# TC364_MainBoard_Power_V1_2.net
KiCad netlist of a schematic drawn in Altium Designer
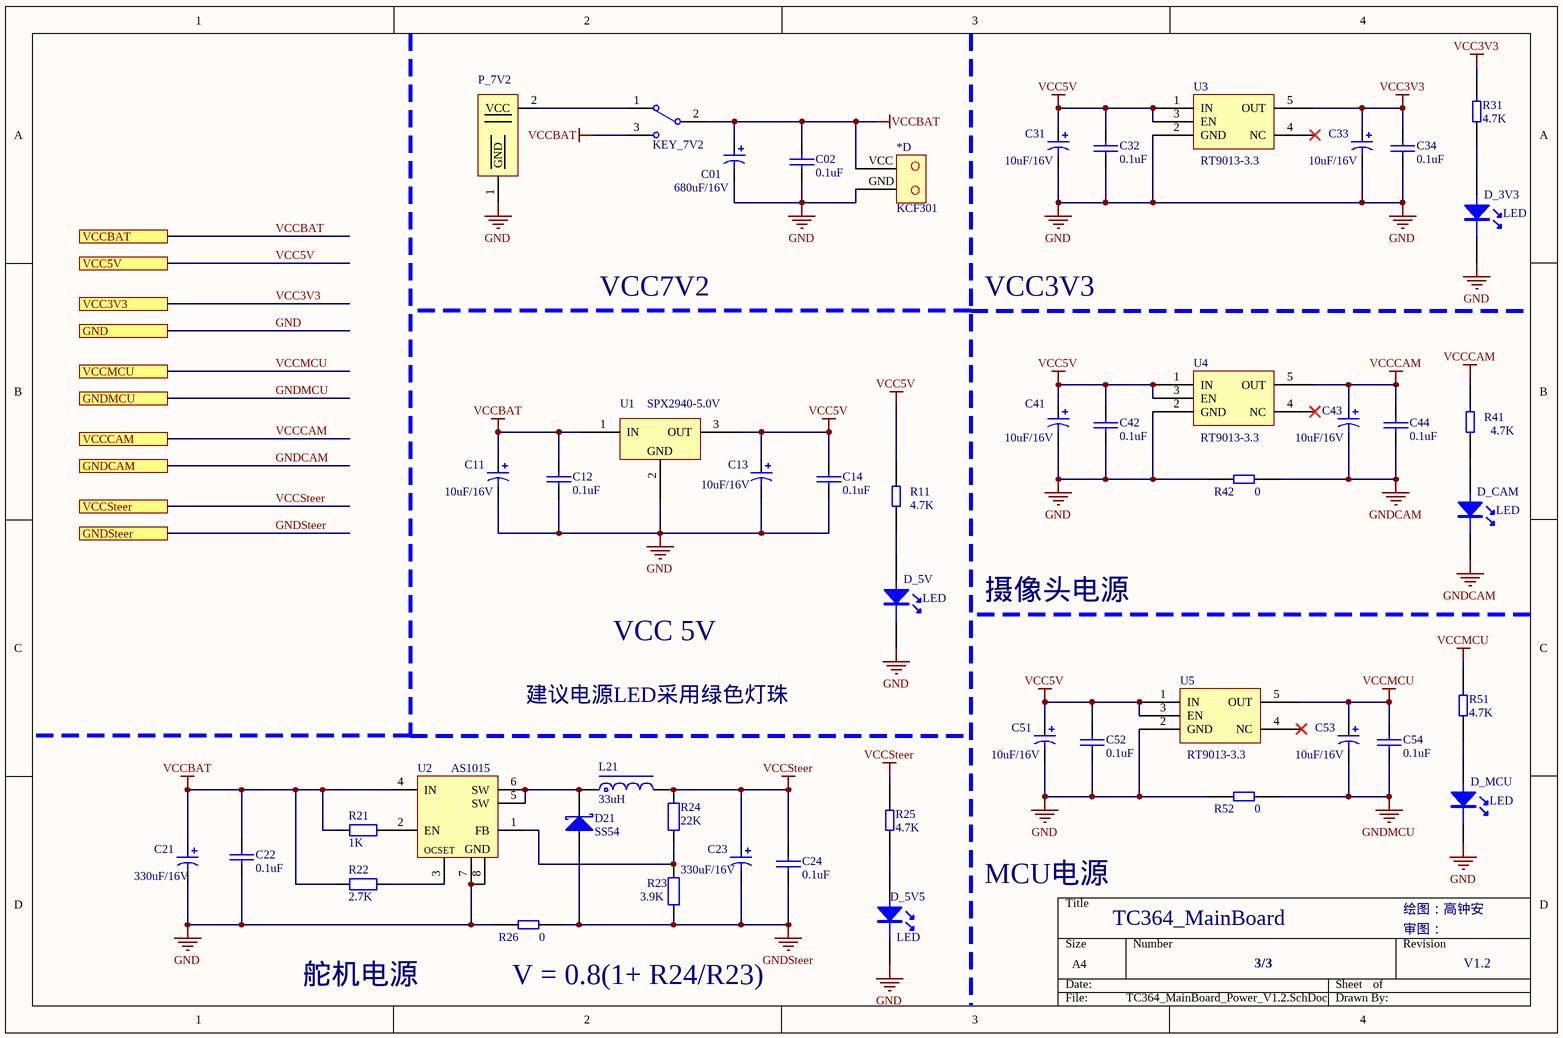
[diagram p0: TC364_MainBoard_Power_V1.2.SchDoc]

(export (version "E")
  (design (tool "Eeschema 10.0.6"))
  (components
    (comp (ref "*") (value "KCF301") (footprint "KF301-2P") (libsource (lib "BaseLib_SCH") (part "KCF301")))
    (comp (ref "C01")
      (value "680uF/16V")
      (footprint "CAP 3.5*8*11.5 - GD")
      (description "Polarized Capacitor (Radial)")
      (fields (field (name "PUBLISHER") "Altium Limited"))
      (libsource (lib "Miscellaneous Devices") (part "Cap Pol1"))
    )
    (comp (ref "C02")
      (value "0.1uF")
      (footprint "0805C")
      (description "Capacitor")
      (libsource (lib "Protel99Lib_SCH") (part "CAP"))
    )
    (comp (ref "C11")
      (value "10uF/16V")
      (footprint "CASE-A_3216")
      (description "Polarized Capacitor (Radial)")
      (fields (field (name "PUBLISHER") "Altium Limited"))
      (libsource (lib "Miscellaneous Devices") (part "Cap Pol1"))
    )
    (comp (ref "C12")
      (value "0.1uF")
      (footprint "0805C")
      (description "Capacitor")
      (libsource (lib "Protel99Lib_SCH") (part "CAP"))
    )
    (comp (ref "C13")
      (value "10uF/16V")
      (footprint "CASE-A_3216")
      (description "Polarized Capacitor (Radial)")
      (fields (field (name "PUBLISHER") "Altium Limited"))
      (libsource (lib "Miscellaneous Devices") (part "Cap Pol1"))
    )
    (comp (ref "C14")
      (value "0.1uF")
      (footprint "0805C")
      (description "Capacitor")
      (libsource (lib "Protel99Lib_SCH") (part "CAP"))
    )
    (comp (ref "C21")
      (value "330uF/16V")
      (footprint "CAP 2.5*6.3*11.2 - BK")
      (description "Polarized Capacitor (Radial)")
      (fields (field (name "PUBLISHER") "Altium Limited"))
      (libsource (lib "Miscellaneous Devices") (part "Cap Pol1"))
    )
    (comp (ref "C22")
      (value "0.1uF")
      (footprint "0805C")
      (description "Capacitor")
      (libsource (lib "Protel99Lib_SCH") (part "CAP"))
    )
    (comp (ref "C23")
      (value "330uF/16V")
      (footprint "CAP 2.5*6.3*11.2 - BK")
      (description "Polarized Capacitor (Radial)")
      (fields (field (name "PUBLISHER") "Altium Limited"))
      (libsource (lib "Miscellaneous Devices") (part "Cap Pol1"))
    )
    (comp (ref "C24")
      (value "0.1uF")
      (footprint "0805C")
      (description "Capacitor")
      (libsource (lib "Protel99Lib_SCH") (part "CAP"))
    )
    (comp (ref "C31")
      (value "10uF/16V")
      (footprint "CASE-A_3216")
      (description "Polarized Capacitor (Radial)")
      (fields (field (name "PUBLISHER") "Altium Limited"))
      (libsource (lib "Miscellaneous Devices") (part "Cap Pol1"))
    )
    (comp (ref "C32")
      (value "0.1uF")
      (footprint "0805C")
      (description "Capacitor")
      (libsource (lib "Protel99Lib_SCH") (part "CAP"))
    )
    (comp (ref "C33")
      (value "10uF/16V")
      (footprint "CASE-A_3216")
      (description "Polarized Capacitor (Radial)")
      (fields (field (name "PUBLISHER") "Altium Limited"))
      (libsource (lib "Miscellaneous Devices") (part "Cap Pol1"))
    )
    (comp (ref "C34")
      (value "0.1uF")
      (footprint "0805C")
      (description "Capacitor")
      (libsource (lib "Protel99Lib_SCH") (part "CAP"))
    )
    (comp (ref "C41")
      (value "10uF/16V")
      (footprint "CASE-A_3216")
      (description "Polarized Capacitor (Radial)")
      (fields (field (name "PUBLISHER") "Altium Limited"))
      (libsource (lib "Miscellaneous Devices") (part "Cap Pol1"))
    )
    (comp (ref "C42")
      (value "0.1uF")
      (footprint "0805C")
      (description "Capacitor")
      (libsource (lib "Protel99Lib_SCH") (part "CAP"))
    )
    (comp (ref "C43")
      (value "10uF/16V")
      (footprint "CASE-A_3216")
      (description "Polarized Capacitor (Radial)")
      (fields (field (name "PUBLISHER") "Altium Limited"))
      (libsource (lib "Miscellaneous Devices") (part "Cap Pol1"))
    )
    (comp (ref "C44")
      (value "0.1uF")
      (footprint "0805C")
      (description "Capacitor")
      (libsource (lib "Protel99Lib_SCH") (part "CAP"))
    )
    (comp (ref "C51")
      (value "10uF/16V")
      (footprint "CASE-A_3216")
      (description "Polarized Capacitor (Radial)")
      (fields (field (name "PUBLISHER") "Altium Limited"))
      (libsource (lib "Miscellaneous Devices") (part "Cap Pol1"))
    )
    (comp (ref "C52")
      (value "0.1uF")
      (footprint "0805C")
      (description "Capacitor")
      (libsource (lib "Protel99Lib_SCH") (part "CAP"))
    )
    (comp (ref "C53")
      (value "10uF/16V")
      (footprint "CASE-A_3216")
      (description "Polarized Capacitor (Radial)")
      (fields (field (name "PUBLISHER") "Altium Limited"))
      (libsource (lib "Miscellaneous Devices") (part "Cap Pol1"))
    )
    (comp (ref "C54")
      (value "0.1uF")
      (footprint "0805C")
      (description "Capacitor")
      (libsource (lib "Protel99Lib_SCH") (part "CAP"))
    )
    (comp (ref "D21")
      (value "SS54")
      (footprint "SMA")
      (description "肖特基二极管")
      (libsource (lib "0.2 -  二极管-整流桥") (part "SS34"))
    )
    (comp (ref "D_3V3")
      (value "LED")
      (footprint "0805_LED_S1")
      (description "发光二极管")
      (libsource (lib "jianing") (part "LED"))
    )
    (comp (ref "D_5V")
      (value "LED")
      (footprint "0805_LED_S1")
      (description "发光二极管")
      (libsource (lib "jianing") (part "LED"))
    )
    (comp (ref "D_5V5")
      (value "LED")
      (footprint "0805_LED_S1")
      (description "发光二极管")
      (libsource (lib "jianing") (part "LED"))
    )
    (comp (ref "D_CAM")
      (value "LED")
      (footprint "0805_LED_S1")
      (description "发光二极管")
      (libsource (lib "jianing") (part "LED"))
    )
    (comp (ref "D_MCU")
      (value "LED")
      (footprint "0805_LED_S1")
      (description "发光二极管")
      (libsource (lib "jianing") (part "LED"))
    )
    (comp (ref "KEY_7V2")
      (value "SS-12F23")
      (footprint "KEY_7V2")
      (description "1路波动开关")
      (fields (field (name "版权归属") "封装库来自淘宝 ID：黄晶宝石"))
      (libsource (lib "0.7 - 常用按键-开关") (part "SSW-1P"))
    )
    (comp (ref "L21")
      (value "33uH")
      (footprint "7*7 L")
      (description "功率屏蔽电感")
      (fields (field (name "版权归属") "封装库来自淘宝 ID：黄晶宝石"))
      (libsource (lib "0.1 - 电阻-电容-电感") (part "L-CDRH"))
    )
    (comp (ref "P_7V2")
      (value "T_Type_Adapter")
      (footprint "T_Type_Adapter")
      (libsource (lib "Schlib1") (part "T_Type_Adapter"))
    )
    (comp (ref "R11") (value "4.7K") (footprint "0805R") (libsource (lib "BaseLib_SCH") (part "RES")))
    (comp (ref "R21")
      (value "1K")
      (footprint "0805R")
      (description "贴片电阻")
      (fields (field (name "版权归属") "源创客"))
      (libsource (lib "jianing") (part "RES"))
    )
    (comp (ref "R22")
      (value "2.7K")
      (footprint "0805R")
      (description "贴片电阻")
      (fields (field (name "版权归属") "源创客"))
      (libsource (lib "jianing") (part "RES"))
    )
    (comp (ref "R23")
      (value "3.9K")
      (footprint "0805R")
      (description "贴片电阻")
      (fields (field (name "版权归属") "源创客"))
      (libsource (lib "jianing") (part "RES"))
    )
    (comp (ref "R24")
      (value "22K")
      (footprint "0805R")
      (description "贴片电阻")
      (fields (field (name "版权归属") "源创客"))
      (libsource (lib "jianing") (part "RES"))
    )
    (comp (ref "R25") (value "4.7K") (footprint "0805R") (libsource (lib "BaseLib_SCH") (part "RES")))
    (comp (ref "R26") (value "0") (footprint "0805R") (libsource (lib "BaseLib_SCH") (part "RES")))
    (comp (ref "R31") (value "4.7K") (footprint "0805R") (libsource (lib "BaseLib_SCH") (part "RES")))
    (comp (ref "R41") (value "4.7K") (footprint "0805R") (libsource (lib "BaseLib_SCH") (part "RES")))
    (comp (ref "R42") (value "0") (footprint "0805R") (libsource (lib "BaseLib_SCH") (part "RES")))
    (comp (ref "R51") (value "4.7K") (footprint "0805R") (libsource (lib "BaseLib_SCH") (part "RES")))
    (comp (ref "R52") (value "0") (footprint "0805R") (libsource (lib "BaseLib_SCH") (part "RES")))
    (comp (ref "U1")
      (value "SPX2940-5.0V")
      (footprint "TO-220(TO-220-3)")
      (description "5V稳压芯片")
      (fields (field (name "版权归属") "封装库来自淘宝 ID：黄晶宝石"))
      (libsource (lib "1.1 - 电源类芯片") (part "LM2940"))
    )
    (comp (ref "U2")
      (value "AS1015")
      (footprint "SOP-8_150mil")
      (description "可调升压芯片")
      (libsource (lib "1.0 - 常见芯片") (part "AS1015"))
    )
    (comp (ref "U3")
      (value "RT9013-3.3")
      (footprint "SOT-23-5")
      (libsource (lib "jianing") (part "RT9013-3.3"))
    )
    (comp (ref "U4")
      (value "RT9013-3.3")
      (footprint "SOT-23-5")
      (libsource (lib "jianing") (part "RT9013-3.3"))
    )
    (comp (ref "U5")
      (value "RT9013-3.3")
      (footprint "SOT-23-5")
      (libsource (lib "jianing") (part "RT9013-3.3"))
    )
  )
  (nets
    (net (code "1") (name "GND") (class "Default")
      (node (ref "C01") (pin "2") (pinfunction "2_2") (pintype "passive"))
      (node (ref "C02") (pin "2") (pinfunction "2_2") (pintype "passive"))
      (node (ref "C11") (pin "2") (pinfunction "2_2") (pintype "passive"))
      (node (ref "C12") (pin "2") (pinfunction "2_2") (pintype "passive"))
      (node (ref "C13") (pin "2") (pinfunction "2_2") (pintype "passive"))
      (node (ref "C14") (pin "2") (pinfunction "2_2") (pintype "passive"))
      (node (ref "C21") (pin "2") (pinfunction "2_2") (pintype "passive"))
      (node (ref "C22") (pin "2") (pinfunction "2_2") (pintype "passive"))
      (node (ref "C31") (pin "2") (pinfunction "2_2") (pintype "passive"))
      (node (ref "C32") (pin "2") (pinfunction "2_2") (pintype "passive"))
      (node (ref "C33") (pin "2") (pinfunction "2_2") (pintype "passive"))
      (node (ref "C34") (pin "2") (pinfunction "2_2") (pintype "passive"))
      (node (ref "C41") (pin "2") (pinfunction "2_2") (pintype "passive"))
      (node (ref "C42") (pin "2") (pinfunction "2_2") (pintype "passive"))
      (node (ref "C51") (pin "2") (pinfunction "2_2") (pintype "passive"))
      (node (ref "C52") (pin "2") (pinfunction "2_2") (pintype "passive"))
      (node (ref "D_3V3") (pin "K") (pinfunction "2_K") (pintype "passive"))
      (node (ref "D_5V") (pin "K") (pinfunction "2_K") (pintype "passive"))
      (node (ref "D_5V5") (pin "K") (pinfunction "2_K") (pintype "passive"))
      (node (ref "P_7V2") (pin "1") (pinfunction "GND_1") (pintype "passive"))
      (node (ref "R26") (pin "2") (pinfunction "2_2") (pintype "passive"))
      (node (ref "R42") (pin "2") (pinfunction "2_2") (pintype "passive"))
      (node (ref "R52") (pin "2") (pinfunction "2_2") (pintype "passive"))
      (node (ref "U1") (pin "2") (pinfunction "GND_2") (pintype "power_in"))
      (node (ref "U2") (pin "7") (pinfunction "GND_7") (pintype "power_in"))
      (node (ref "U2") (pin "8") (pinfunction "GND_8") (pintype "power_in"))
      (node (ref "U3") (pin "2") (pinfunction "GND_2") (pintype "passive"))
      (node (ref "U4") (pin "2") (pinfunction "GND_2") (pintype "passive"))
      (node (ref "U5") (pin "2") (pinfunction "GND_2") (pintype "passive"))
    )
    (net (code "2") (name "GNDCAM") (class "Default")
      (node (ref "C43") (pin "2") (pinfunction "2_2") (pintype "passive"))
      (node (ref "C44") (pin "2") (pinfunction "2_2") (pintype "passive"))
      (node (ref "D_CAM") (pin "K") (pinfunction "2_K") (pintype "passive"))
      (node (ref "R42") (pin "1") (pinfunction "1_1") (pintype "passive"))
    )
    (net (code "3") (name "GNDMCU") (class "Default")
      (node (ref "C53") (pin "2") (pinfunction "2_2") (pintype "passive"))
      (node (ref "C54") (pin "2") (pinfunction "2_2") (pintype "passive"))
      (node (ref "R52") (pin "1") (pinfunction "1_1") (pintype "passive"))
    )
    (net (code "4") (name "GNDSteer") (class "Default")
      (node (ref "C23") (pin "2") (pinfunction "2_2") (pintype "passive"))
      (node (ref "C24") (pin "2") (pinfunction "2_2") (pintype "passive"))
      (node (ref "D21") (pin "1") (pinfunction "A_1") (pintype "passive"))
      (node (ref "R23") (pin "2") (pinfunction "2_2") (pintype "passive"))
      (node (ref "R26") (pin "1") (pinfunction "1_1") (pintype "passive"))
    )
    (net (code "5") (name "Net-(D21-K)") (class "Default")
      (node (ref "D21") (pin "2") (pinfunction "K_2") (pintype "passive"))
      (node (ref "L21") (pin "1") (pinfunction "1_1") (pintype "passive"))
      (node (ref "U2") (pin "5") (pinfunction "SW_5") (pintype "power_in"))
      (node (ref "U2") (pin "6") (pinfunction "SW_6") (pintype "power_in"))
    )
    (net (code "6") (name "Net-(D_3V3-1)") (class "Default")
      (node (ref "D_3V3") (pin "A") (pinfunction "1_A") (pintype "passive"))
      (node (ref "R31") (pin "2") (pinfunction "2_2") (pintype "passive"))
    )
    (net (code "7") (name "Net-(D_5V-1)") (class "Default")
      (node (ref "D_5V") (pin "A") (pinfunction "1_A") (pintype "passive"))
      (node (ref "R11") (pin "2") (pinfunction "2_2") (pintype "passive"))
    )
    (net (code "8") (name "Net-(D_5V5-1)") (class "Default")
      (node (ref "D_5V5") (pin "A") (pinfunction "1_A") (pintype "passive"))
      (node (ref "R25") (pin "2") (pinfunction "2_2") (pintype "passive"))
    )
    (net (code "9") (name "Net-(D_CAM-1)") (class "Default")
      (node (ref "D_CAM") (pin "A") (pinfunction "1_A") (pintype "passive"))
      (node (ref "R41") (pin "2") (pinfunction "2_2") (pintype "passive"))
    )
    (net (code "10") (name "Net-(D_MCU-1)") (class "Default")
      (node (ref "D_MCU") (pin "A") (pinfunction "1_A") (pintype "passive"))
      (node (ref "R51") (pin "2") (pinfunction "2_2") (pintype "passive"))
    )
    (net (code "11") (name "Net-(P_7V2-VCC)") (class "Default")
      (node (ref "KEY_7V2") (pin "1") (pinfunction "1_1") (pintype "passive"))
      (node (ref "P_7V2") (pin "2") (pinfunction "VCC_2") (pintype "passive"))
    )
    (net (code "12") (name "Net-(U2-EN)") (class "Default")
      (node (ref "R21") (pin "1") (pinfunction "1_1") (pintype "passive"))
      (node (ref "U2") (pin "2") (pinfunction "EN_2") (pintype "power_in"))
    )
    (net (code "13") (name "Net-(U2-FB)") (class "Default")
      (node (ref "R23") (pin "1") (pinfunction "1_1") (pintype "passive"))
      (node (ref "R24") (pin "2") (pinfunction "2_2") (pintype "passive"))
      (node (ref "U2") (pin "1") (pinfunction "FB_1") (pintype "power_in"))
    )
    (net (code "14") (name "Net-(U2-OCSET)") (class "Default")
      (node (ref "R22") (pin "1") (pinfunction "1_1") (pintype "passive"))
      (node (ref "U2") (pin "3") (pinfunction "OCSET_3") (pintype "power_in"))
    )
    (net (code "15") (name "VCC3V3") (class "Default")
      (node (ref "C33") (pin "1") (pinfunction "1_1") (pintype "passive"))
      (node (ref "C34") (pin "1") (pinfunction "1_1") (pintype "passive"))
      (node (ref "R31") (pin "1") (pinfunction "1_1") (pintype "passive"))
      (node (ref "U3") (pin "5") (pinfunction "OUT_5") (pintype "passive"))
    )
    (net (code "16") (name "VCC5V") (class "Default")
      (node (ref "C13") (pin "1") (pinfunction "1_1") (pintype "passive"))
      (node (ref "C14") (pin "1") (pinfunction "1_1") (pintype "passive"))
      (node (ref "C31") (pin "1") (pinfunction "1_1") (pintype "passive"))
      (node (ref "C32") (pin "1") (pinfunction "1_1") (pintype "passive"))
      (node (ref "C41") (pin "1") (pinfunction "1_1") (pintype "passive"))
      (node (ref "C42") (pin "1") (pinfunction "1_1") (pintype "passive"))
      (node (ref "C51") (pin "1") (pinfunction "1_1") (pintype "passive"))
      (node (ref "C52") (pin "1") (pinfunction "1_1") (pintype "passive"))
      (node (ref "R11") (pin "1") (pinfunction "1_1") (pintype "passive"))
      (node (ref "U1") (pin "3") (pinfunction "OUT_3") (pintype "power_in"))
      (node (ref "U3") (pin "1") (pinfunction "IN_1") (pintype "passive"))
      (node (ref "U3") (pin "3") (pinfunction "EN_3") (pintype "passive"))
      (node (ref "U4") (pin "1") (pinfunction "IN_1") (pintype "passive"))
      (node (ref "U4") (pin "3") (pinfunction "EN_3") (pintype "passive"))
      (node (ref "U5") (pin "1") (pinfunction "IN_1") (pintype "passive"))
      (node (ref "U5") (pin "3") (pinfunction "EN_3") (pintype "passive"))
    )
    (net (code "17") (name "VCCBAT") (class "Default")
      (node (ref "C01") (pin "1") (pinfunction "1_1") (pintype "passive"))
      (node (ref "C02") (pin "1") (pinfunction "1_1") (pintype "passive"))
      (node (ref "C11") (pin "1") (pinfunction "1_1") (pintype "passive"))
      (node (ref "C12") (pin "1") (pinfunction "1_1") (pintype "passive"))
      (node (ref "C21") (pin "1") (pinfunction "1_1") (pintype "passive"))
      (node (ref "C22") (pin "1") (pinfunction "1_1") (pintype "passive"))
      (node (ref "KEY_7V2") (pin "2") (pinfunction "2_2") (pintype "passive"))
      (node (ref "KEY_7V2") (pin "3") (pinfunction "3_3") (pintype "passive"))
      (node (ref "R21") (pin "2") (pinfunction "2_2") (pintype "passive"))
      (node (ref "R22") (pin "2") (pinfunction "2_2") (pintype "passive"))
      (node (ref "U1") (pin "1") (pinfunction "IN_1") (pintype "power_in"))
      (node (ref "U2") (pin "4") (pinfunction "IN_4") (pintype "power_in"))
    )
    (net (code "18") (name "VCCCAM") (class "Default")
      (node (ref "C43") (pin "1") (pinfunction "1_1") (pintype "passive"))
      (node (ref "C44") (pin "1") (pinfunction "1_1") (pintype "passive"))
      (node (ref "R41") (pin "1") (pinfunction "1_1") (pintype "passive"))
      (node (ref "U4") (pin "5") (pinfunction "OUT_5") (pintype "passive"))
    )
    (net (code "19") (name "VCCMCU") (class "Default")
      (node (ref "C53") (pin "1") (pinfunction "1_1") (pintype "passive"))
      (node (ref "C54") (pin "1") (pinfunction "1_1") (pintype "passive"))
      (node (ref "R51") (pin "1") (pinfunction "1_1") (pintype "passive"))
      (node (ref "U5") (pin "5") (pinfunction "OUT_5") (pintype "passive"))
    )
    (net (code "20") (name "VCCSteer") (class "Default")
      (node (ref "C23") (pin "1") (pinfunction "1_1") (pintype "passive"))
      (node (ref "C24") (pin "1") (pinfunction "1_1") (pintype "passive"))
      (node (ref "L21") (pin "2") (pinfunction "2_2") (pintype "passive"))
      (node (ref "R24") (pin "1") (pinfunction "1_1") (pintype "passive"))
      (node (ref "R25") (pin "1") (pinfunction "1_1") (pintype "passive"))
    )
    (net (code "21") (name "unconnected-(*D-0-PadVCC)") (class "Default")
      (node (ref "*") (pin "VCC") (pinfunction "0_VCC") (pintype "passive"))
    )
    (net (code "22") (name "unconnected-(*D-1-PadGND)") (class "Default")
      (node (ref "*") (pin "GND") (pinfunction "1_GND") (pintype "passive"))
    )
    (net (code "23") (name "unconnected-(D_MCU-2-PadK)") (class "Default")
      (node (ref "D_MCU") (pin "K") (pinfunction "2_K") (pintype "passive"))
    )
    (net (code "24") (name "unconnected-(U3-NC-Pad4)") (class "Default")
      (node (ref "U3") (pin "4") (pinfunction "NC_4") (pintype "passive+no_connect"))
    )
    (net (code "25") (name "unconnected-(U4-NC-Pad4)") (class "Default")
      (node (ref "U4") (pin "4") (pinfunction "NC_4") (pintype "passive+no_connect"))
    )
    (net (code "26") (name "unconnected-(U5-NC-Pad4)") (class "Default")
      (node (ref "U5") (pin "4") (pinfunction "NC_4") (pintype "passive+no_connect"))
    )
  )
)
